# design.net
KiCad netlist of a schematic drawn in EasyEDA Pro
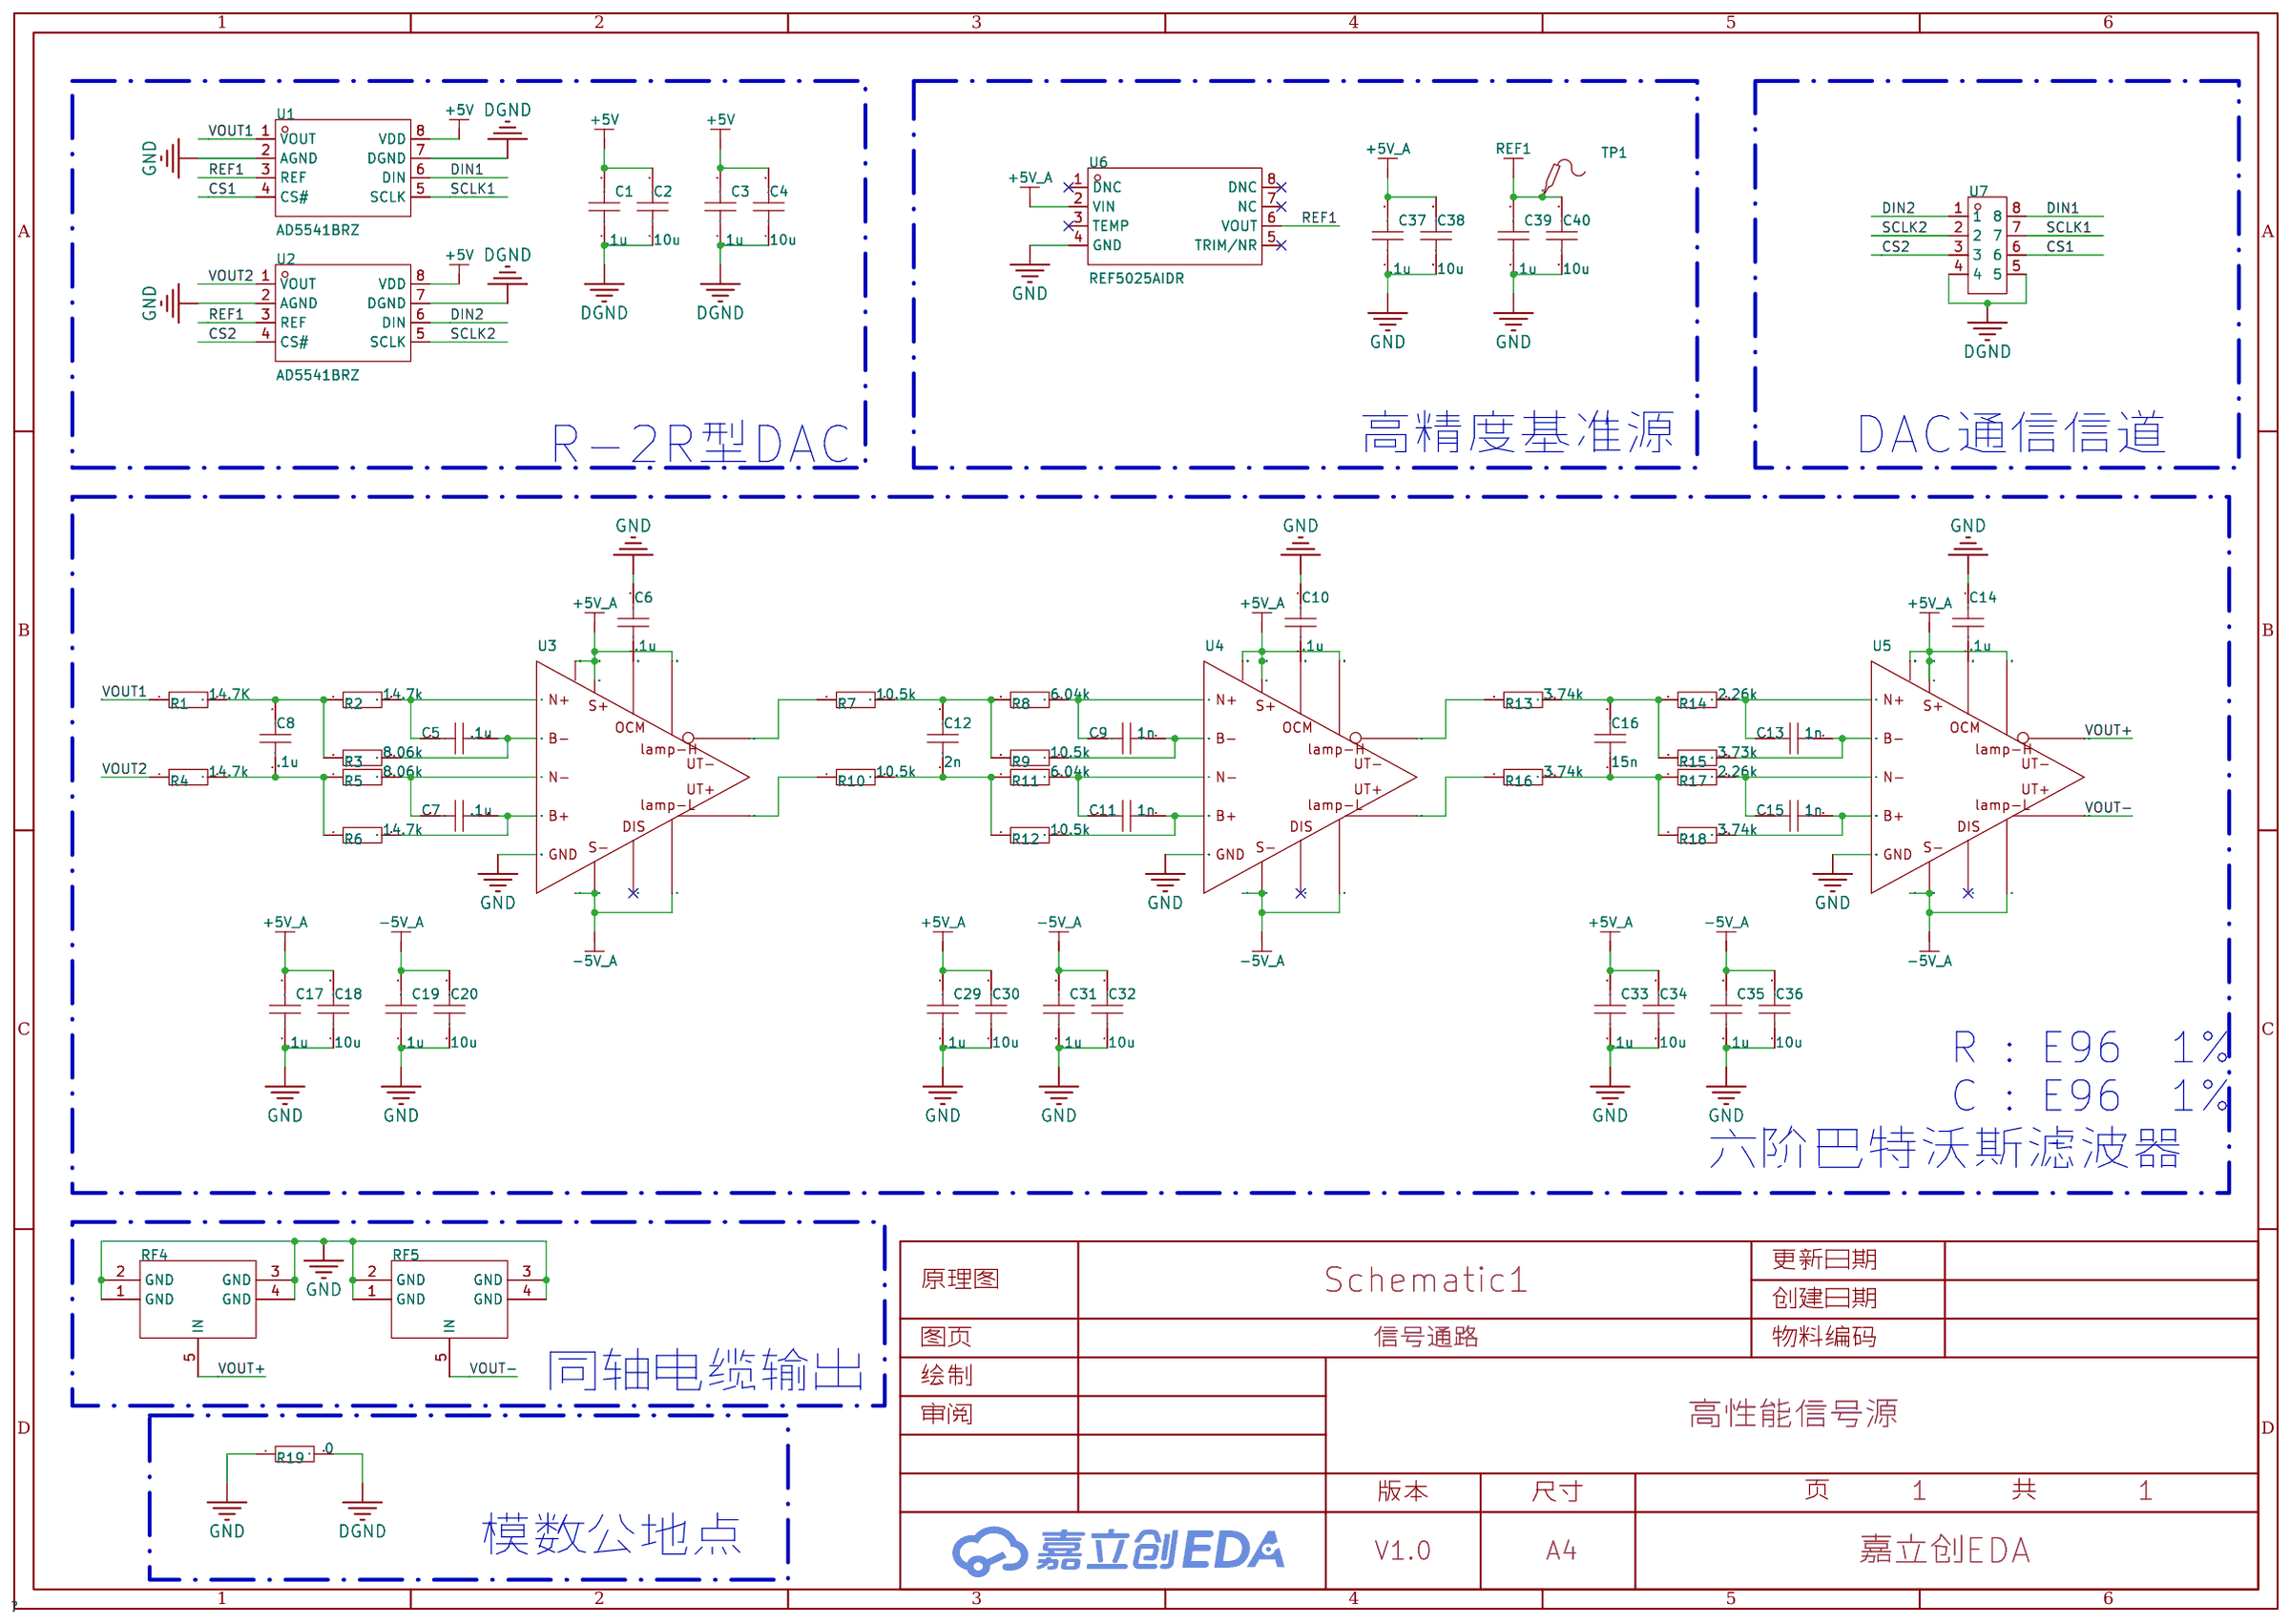
[diagram p0: 信号通路]
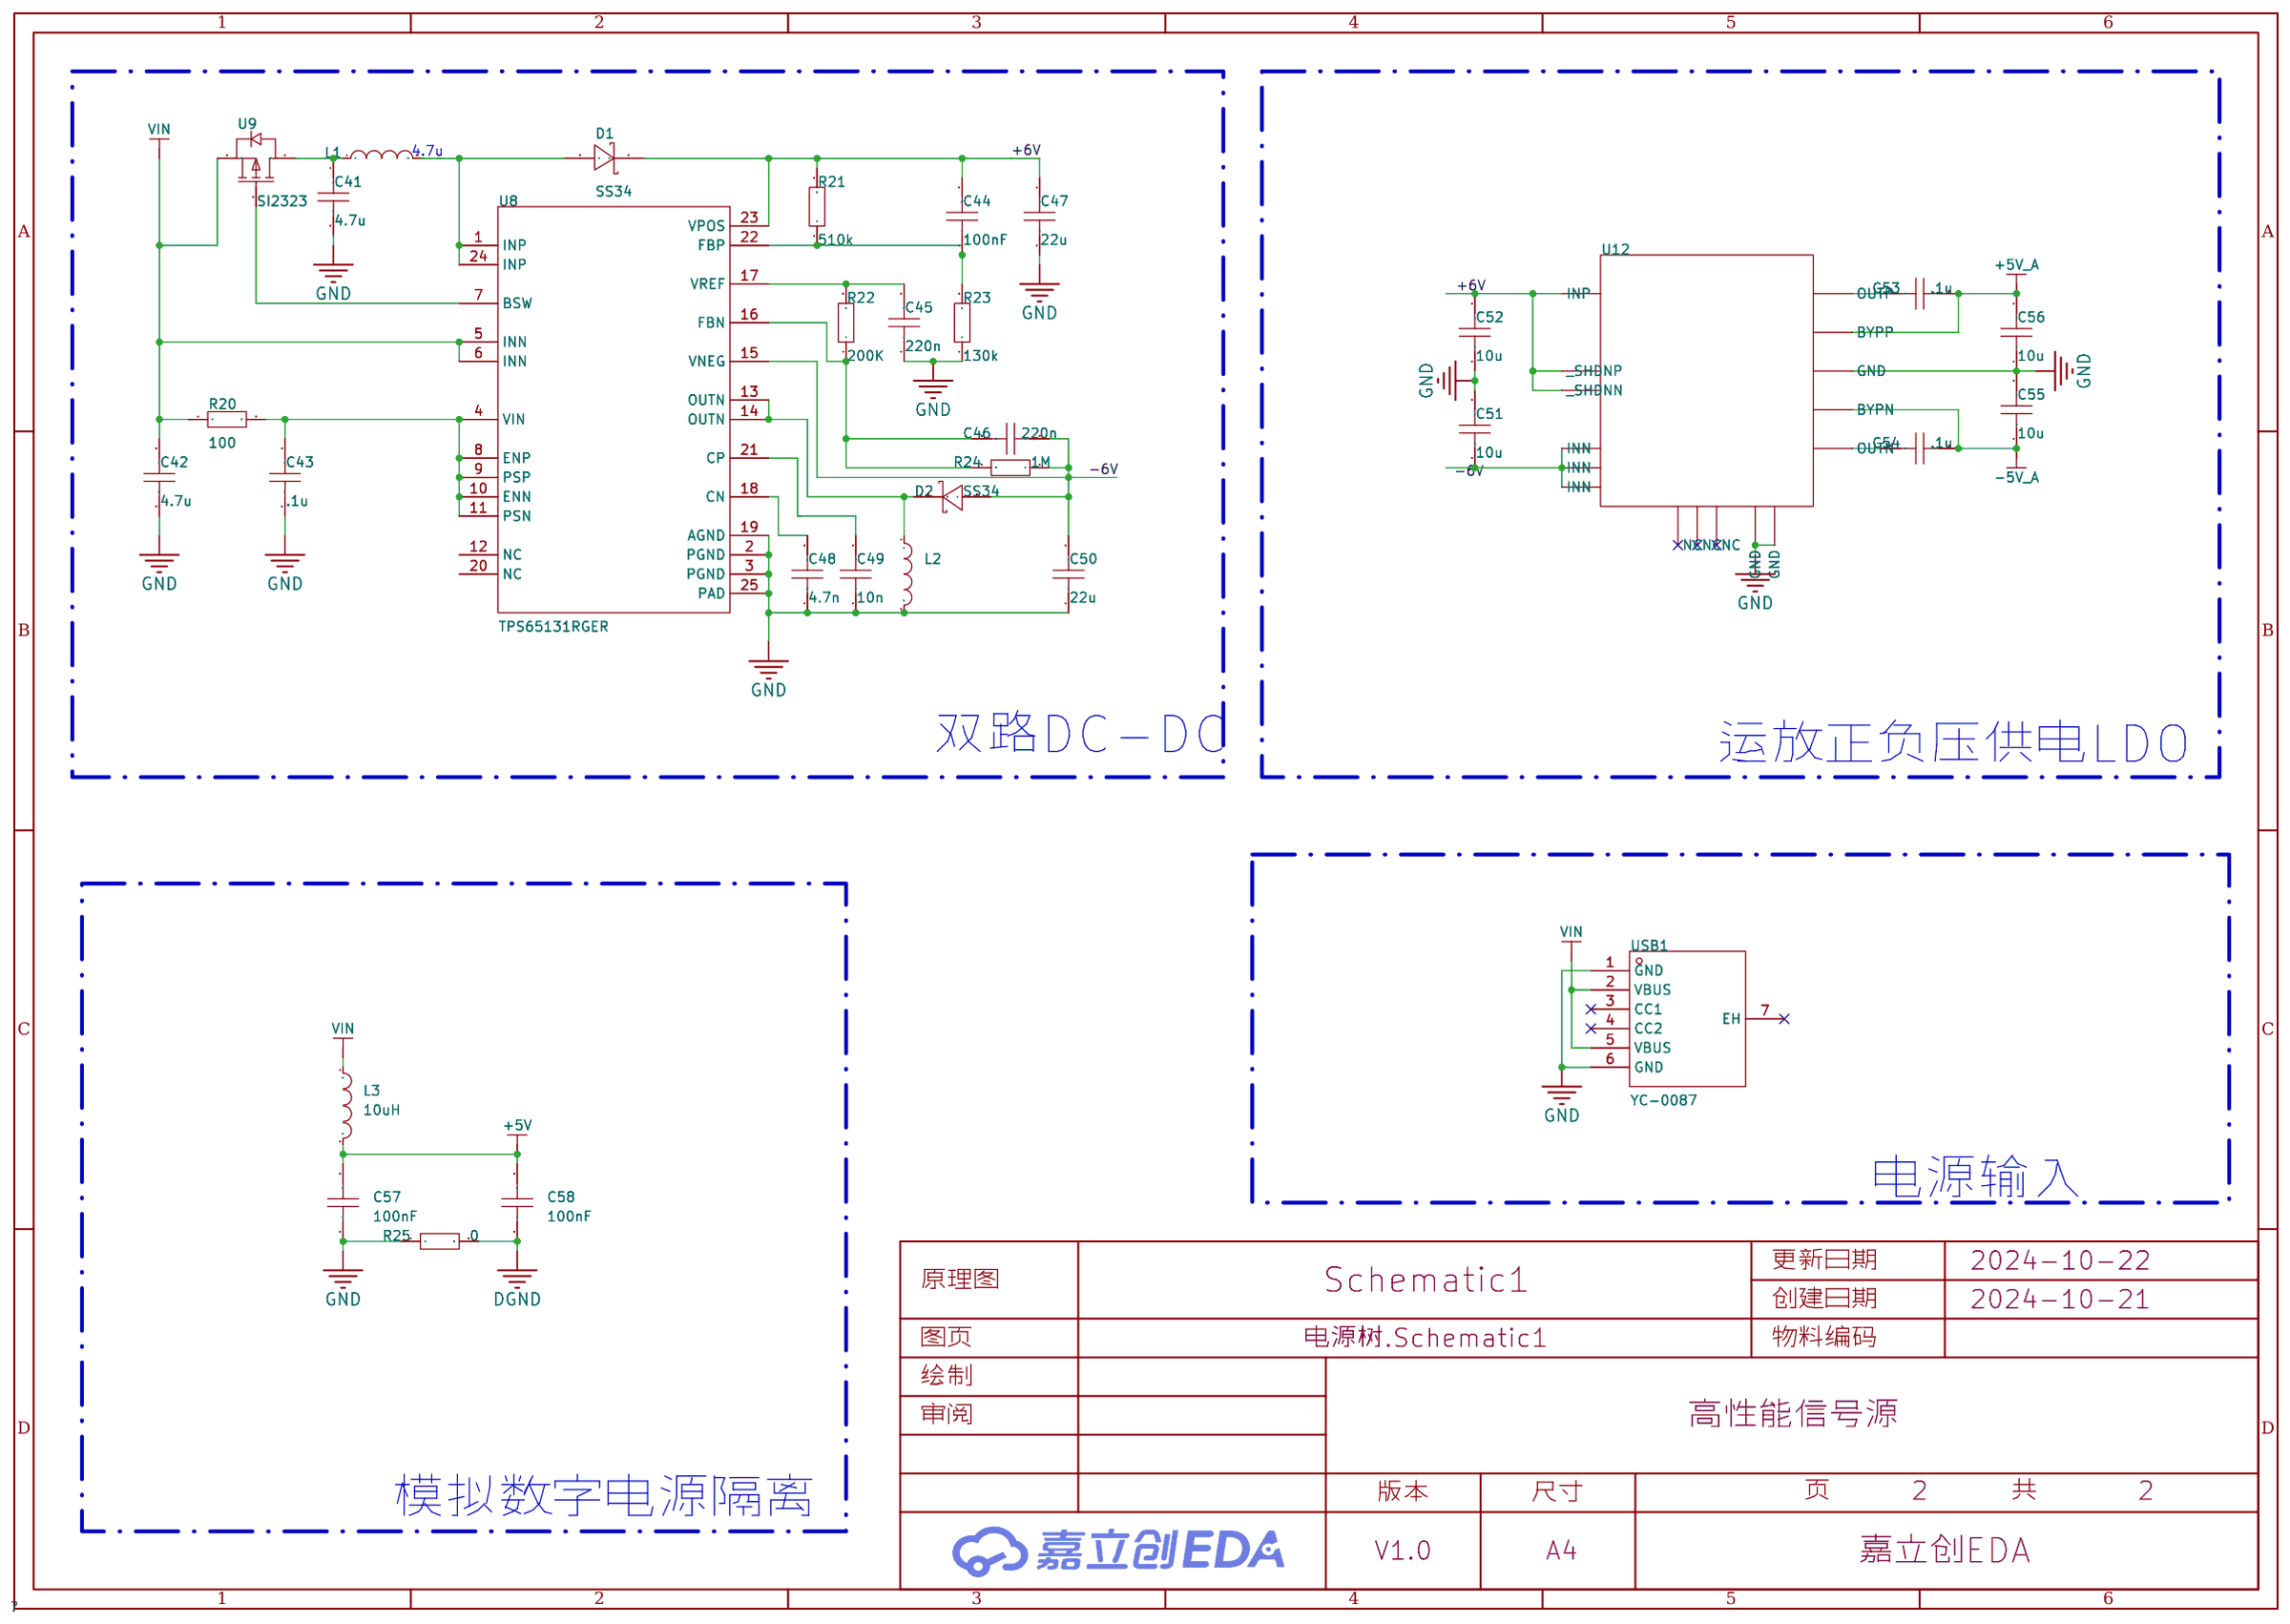
[diagram p1: 电源树]

(export (version "E")
  (design (tool "Eeschema 10.0.6"))
  (components
    (comp (ref "C1")
      (value ".1u")
      (footprint "easyedapro:C0603")
      (libsource (lib "easyedapro") (part "CapAcitance"))
    )
    (comp (ref "C2")
      (value "10u")
      (footprint "easyedapro:C0603")
      (libsource (lib "easyedapro") (part "CapAcitance"))
    )
    (comp (ref "C3")
      (value ".1u")
      (footprint "easyedapro:C0603")
      (libsource (lib "easyedapro") (part "CapAcitance"))
    )
    (comp (ref "C4")
      (value "10u")
      (footprint "easyedapro:C0603")
      (libsource (lib "easyedapro") (part "CapAcitance"))
    )
    (comp (ref "C5")
      (value ".1u")
      (footprint "easyedapro:C0603")
      (libsource (lib "easyedapro") (part "CapAcitance"))
    )
    (comp (ref "C6")
      (value ".1u")
      (footprint "easyedapro:C0603")
      (libsource (lib "easyedapro") (part "CapAcitance"))
    )
    (comp (ref "C7")
      (value ".1u")
      (footprint "easyedapro:C0603")
      (libsource (lib "easyedapro") (part "CapAcitance"))
    )
    (comp (ref "C8")
      (value ".1u")
      (footprint "easyedapro:C0603")
      (libsource (lib "easyedapro") (part "CapAcitance"))
    )
    (comp (ref "C9")
      (value "1n")
      (footprint "easyedapro:C0603")
      (libsource (lib "easyedapro") (part "CapAcitance"))
    )
    (comp (ref "C10")
      (value ".1u")
      (footprint "easyedapro:C0603")
      (libsource (lib "easyedapro") (part "CapAcitance"))
    )
    (comp (ref "C11")
      (value "1n")
      (footprint "easyedapro:C0603")
      (libsource (lib "easyedapro") (part "CapAcitance"))
    )
    (comp (ref "C12")
      (value "2n")
      (footprint "easyedapro:C0603")
      (libsource (lib "easyedapro") (part "CapAcitance"))
    )
    (comp (ref "C13")
      (value "1n")
      (footprint "easyedapro:C0603")
      (libsource (lib "easyedapro") (part "CapAcitance"))
    )
    (comp (ref "C14")
      (value ".1u")
      (footprint "easyedapro:C0603")
      (libsource (lib "easyedapro") (part "CapAcitance"))
    )
    (comp (ref "C15")
      (value "1n")
      (footprint "easyedapro:C0603")
      (libsource (lib "easyedapro") (part "CapAcitance"))
    )
    (comp (ref "C16")
      (value "15n")
      (footprint "easyedapro:C0603")
      (libsource (lib "easyedapro") (part "CapAcitance"))
    )
    (comp (ref "C17")
      (value ".1u")
      (footprint "easyedapro:C0603")
      (libsource (lib "easyedapro") (part "CapAcitance"))
    )
    (comp (ref "C18")
      (value "10u")
      (footprint "easyedapro:C0603")
      (libsource (lib "easyedapro") (part "CapAcitance"))
    )
    (comp (ref "C19")
      (value ".1u")
      (footprint "easyedapro:C0603")
      (libsource (lib "easyedapro") (part "CapAcitance"))
    )
    (comp (ref "C20")
      (value "10u")
      (footprint "easyedapro:C0603")
      (libsource (lib "easyedapro") (part "CapAcitance"))
    )
    (comp (ref "C29")
      (value ".1u")
      (footprint "easyedapro:C0603")
      (libsource (lib "easyedapro") (part "CapAcitance"))
    )
    (comp (ref "C30")
      (value "10u")
      (footprint "easyedapro:C0603")
      (libsource (lib "easyedapro") (part "CapAcitance"))
    )
    (comp (ref "C31")
      (value ".1u")
      (footprint "easyedapro:C0603")
      (libsource (lib "easyedapro") (part "CapAcitance"))
    )
    (comp (ref "C32")
      (value "10u")
      (footprint "easyedapro:C0603")
      (libsource (lib "easyedapro") (part "CapAcitance"))
    )
    (comp (ref "C33")
      (value ".1u")
      (footprint "easyedapro:C0603")
      (libsource (lib "easyedapro") (part "CapAcitance"))
    )
    (comp (ref "C34")
      (value "10u")
      (footprint "easyedapro:C0603")
      (libsource (lib "easyedapro") (part "CapAcitance"))
    )
    (comp (ref "C35")
      (value ".1u")
      (footprint "easyedapro:C0603")
      (libsource (lib "easyedapro") (part "CapAcitance"))
    )
    (comp (ref "C36")
      (value "10u")
      (footprint "easyedapro:C0603")
      (libsource (lib "easyedapro") (part "CapAcitance"))
    )
    (comp (ref "C37")
      (value ".1u")
      (footprint "easyedapro:C0603")
      (libsource (lib "easyedapro") (part "CapAcitance"))
    )
    (comp (ref "C38")
      (value "10u")
      (footprint "easyedapro:C0603")
      (libsource (lib "easyedapro") (part "CapAcitance"))
    )
    (comp (ref "C39")
      (value ".1u")
      (footprint "easyedapro:C0603")
      (libsource (lib "easyedapro") (part "CapAcitance"))
    )
    (comp (ref "C40")
      (value "10u")
      (footprint "easyedapro:C0603")
      (libsource (lib "easyedapro") (part "CapAcitance"))
    )
    (comp (ref "R1")
      (value "14.7K")
      (footprint "easyedapro:R0603")
      (libsource (lib "easyedapro") (part "电阻"))
    )
    (comp (ref "R2")
      (value "14.7k")
      (footprint "easyedapro:R0603")
      (libsource (lib "easyedapro") (part "电阻"))
    )
    (comp (ref "R3")
      (value "8.06k")
      (footprint "easyedapro:R0603")
      (libsource (lib "easyedapro") (part "电阻"))
    )
    (comp (ref "R4")
      (value "14.7k")
      (footprint "easyedapro:R0603")
      (libsource (lib "easyedapro") (part "电阻"))
    )
    (comp (ref "R5")
      (value "8.06k")
      (footprint "easyedapro:R0603")
      (libsource (lib "easyedapro") (part "电阻"))
    )
    (comp (ref "R6")
      (value "14.7k")
      (footprint "easyedapro:R0603")
      (libsource (lib "easyedapro") (part "电阻"))
    )
    (comp (ref "R7")
      (value "10.5k")
      (footprint "easyedapro:R0603")
      (libsource (lib "easyedapro") (part "电阻"))
    )
    (comp (ref "R8")
      (value "6.04k")
      (footprint "easyedapro:R0603")
      (libsource (lib "easyedapro") (part "电阻"))
    )
    (comp (ref "R9")
      (value "10.5k")
      (footprint "easyedapro:R0603")
      (libsource (lib "easyedapro") (part "电阻"))
    )
    (comp (ref "R10")
      (value "10.5k")
      (footprint "easyedapro:R0603")
      (libsource (lib "easyedapro") (part "电阻"))
    )
    (comp (ref "R11")
      (value "6.04k")
      (footprint "easyedapro:R0603")
      (libsource (lib "easyedapro") (part "电阻"))
    )
    (comp (ref "R12")
      (value "10.5k")
      (footprint "easyedapro:R0603")
      (libsource (lib "easyedapro") (part "电阻"))
    )
    (comp (ref "R13")
      (value "3.74k")
      (footprint "easyedapro:R0603")
      (libsource (lib "easyedapro") (part "电阻"))
    )
    (comp (ref "R14")
      (value "2.26k")
      (footprint "easyedapro:R0603")
      (libsource (lib "easyedapro") (part "电阻"))
    )
    (comp (ref "R15")
      (value "3.73k")
      (footprint "easyedapro:R0603")
      (libsource (lib "easyedapro") (part "电阻"))
    )
    (comp (ref "R16")
      (value "3.74k")
      (footprint "easyedapro:R0603")
      (libsource (lib "easyedapro") (part "电阻"))
    )
    (comp (ref "R17")
      (value "2.26k")
      (footprint "easyedapro:R0603")
      (libsource (lib "easyedapro") (part "电阻"))
    )
    (comp (ref "R18")
      (value "3.74k")
      (footprint "easyedapro:R0603")
      (libsource (lib "easyedapro") (part "电阻"))
    )
    (comp (ref "R19") (value "0") (footprint "easyedapro:R0603") (libsource (lib "easyedapro") (part "电阻")))
    (comp (ref "RF4")
      (value "KH-SMA-K513-G")
      (footprint "easyedapro:ANT-TH_KH-SMA-K513-G")
      (description "连接器类型:板端;接口类型:内孔;端口数量:1;接口直径:-;接口长度/高度:-;频率-最大值:6GHz;射频系列:SMA;阻抗:50Ω;样式:弯头;工作温度范围:-55°C~+155°C;")
      (fields (field (name "Manufacturer") "kinghelm(金航标)"))
      (libsource (lib "easyedapro") (part "KH-SMA-K513-G"))
    )
    (comp (ref "RF5")
      (value "KH-SMA-K513-G")
      (footprint "easyedapro:ANT-TH_KH-SMA-K513-G")
      (description "连接器类型:板端;接口类型:内孔;端口数量:1;接口直径:-;接口长度/高度:-;频率-最大值:6GHz;射频系列:SMA;阻抗:50Ω;样式:弯头;工作温度范围:-55°C~+155°C;")
      (fields (field (name "Manufacturer") "kinghelm(金航标)"))
      (libsource (lib "easyedapro") (part "KH-SMA-K513-G"))
    )
    (comp (ref "TP1")
      (value "~")
      (footprint "easyedapro:Test-Point-0.5mm")
      (description "Test Point 测试点")
      (libsource (lib "easyedapro") (part "Test-Point"))
    )
    (comp (ref "U1")
      (value "AD5541BRZ")
      (footprint "easyedapro:SOIC-8_L4.9-W3.9-P1.27-LS6.0-BL")
      (description "接口:DSP；SPI;电源电压:2.7V~5.5V;分辨率:16位;INL/DNL:±0.5LSB；±0.5LSB;稳定时间:1us;")
      (fields (field (name "Manufacturer") "ADI(亚德诺)"))
      (libsource (lib "easyedapro") (part "AD5541BRZ"))
    )
    (comp (ref "U2")
      (value "AD5541BRZ")
      (footprint "easyedapro:SOIC-8_L4.9-W3.9-P1.27-LS6.0-BL")
      (description "接口:DSP；SPI;电源电压:2.7V~5.5V;分辨率:16位;INL/DNL:±0.5LSB；±0.5LSB;稳定时间:1us;")
      (fields (field (name "Manufacturer") "ADI(亚德诺)"))
      (libsource (lib "easyedapro") (part "AD5541BRZ"))
    )
    (comp (ref "U3")
      (value "~")
      (footprint "easyedapro:LFCSP-16_L3.0-W3.0-P0.50-TL-EP1.6-1")
      (libsource (lib "easyedapro") (part "ADA4945-HP"))
    )
    (comp (ref "U4")
      (value "~")
      (footprint "easyedapro:LFCSP-16_L3.0-W3.0-P0.50-TL-EP1.6-1")
      (libsource (lib "easyedapro") (part "ADA4945-HP"))
    )
    (comp (ref "U5")
      (value "~")
      (footprint "easyedapro:LFCSP-16_L3.0-W3.0-P0.50-TL-EP1.6-1")
      (libsource (lib "easyedapro") (part "ADA4945-HP"))
    )
    (comp (ref "U6")
      (value "REF5025AIDR")
      (footprint "easyedapro:SOIC-8_L4.9-W3.9-P1.27-LS6.0-BL")
      (description "输出类型:固定;输入电压:2.7V~18V;输出电压:2.5V;输出电流:10mA;精度:±0.1%;")
      (fields (field (name "Manufacturer") "TI(德州仪器)"))
      (libsource (lib "easyedapro") (part "REF5025AIDR"))
    )
    (comp (ref "U7")
      (value "~")
      (footprint "easyedapro:母针座2.54 2X4")
      (libsource (lib "easyedapro") (part "母针座2.54 8P"))
    )
    (comp (ref "C41")
      (value "4.7u")
      (footprint "easyedapro:C0603")
      (libsource (lib "easyedapro") (part "CapAcitance"))
    )
    (comp (ref "C42")
      (value "4.7u")
      (footprint "easyedapro:C0603")
      (libsource (lib "easyedapro") (part "CapAcitance"))
    )
    (comp (ref "C43")
      (value ".1u")
      (footprint "easyedapro:C0603")
      (libsource (lib "easyedapro") (part "CapAcitance"))
    )
    (comp (ref "C44")
      (value "100nF")
      (footprint "easyedapro:C0603")
      (libsource (lib "easyedapro") (part "CapAcitance"))
    )
    (comp (ref "C45")
      (value "220n")
      (footprint "easyedapro:C0603")
      (libsource (lib "easyedapro") (part "CapAcitance"))
    )
    (comp (ref "C46")
      (value "220n")
      (footprint "easyedapro:C0603")
      (libsource (lib "easyedapro") (part "CapAcitance"))
    )
    (comp (ref "C47")
      (value "22u")
      (footprint "easyedapro:C0603")
      (libsource (lib "easyedapro") (part "CapAcitance"))
    )
    (comp (ref "C48")
      (value "4.7n")
      (footprint "easyedapro:C0603")
      (libsource (lib "easyedapro") (part "CapAcitance"))
    )
    (comp (ref "C49")
      (value "10n")
      (footprint "easyedapro:C0603")
      (libsource (lib "easyedapro") (part "CapAcitance"))
    )
    (comp (ref "C50")
      (value "22u")
      (footprint "easyedapro:C0603")
      (libsource (lib "easyedapro") (part "CapAcitance"))
    )
    (comp (ref "C51")
      (value "10u")
      (footprint "easyedapro:C0603")
      (libsource (lib "easyedapro") (part "CapAcitance"))
    )
    (comp (ref "C52")
      (value "10u")
      (footprint "easyedapro:C0603")
      (libsource (lib "easyedapro") (part "CapAcitance"))
    )
    (comp (ref "C53")
      (value ".1u")
      (footprint "easyedapro:C0603")
      (libsource (lib "easyedapro") (part "CapAcitance"))
    )
    (comp (ref "C54")
      (value ".1u")
      (footprint "easyedapro:C0603")
      (libsource (lib "easyedapro") (part "CapAcitance"))
    )
    (comp (ref "C55")
      (value "10u")
      (footprint "easyedapro:C0603")
      (libsource (lib "easyedapro") (part "CapAcitance"))
    )
    (comp (ref "C56")
      (value "10u")
      (footprint "easyedapro:C0603")
      (libsource (lib "easyedapro") (part "CapAcitance"))
    )
    (comp (ref "C57")
      (value "100nF")
      (footprint "easyedapro:C0603")
      (libsource (lib "easyedapro") (part "CapAcitance"))
    )
    (comp (ref "C58")
      (value "100nF")
      (footprint "easyedapro:C0603")
      (libsource (lib "easyedapro") (part "CapAcitance"))
    )
    (comp (ref "D1")
      (value "SS34")
      (footprint "easyedapro:SMA_L4.3-W2.6-LS5.2-RD")
      (description "二极管配置:独立式;正向压降(Vf):550mV@3A;直流反向耐压(Vr):40V;整流电流:3A;")
      (fields (field (name "Manufacturer") "MDD(辰达半导体)"))
      (libsource (lib "easyedapro") (part "SS34_C8678"))
    )
    (comp (ref "D2")
      (value "SS34")
      (footprint "easyedapro:SMA_L4.3-W2.6-LS5.2-RD")
      (description "二极管配置:独立式;正向压降(Vf):550mV@3A;直流反向耐压(Vr):40V;整流电流:3A;")
      (fields (field (name "Manufacturer") "MDD(辰达半导体)"))
      (libsource (lib "easyedapro") (part "SS34_C8678"))
    )
    (comp (ref "L1")
      (value "~")
      (footprint "easyedapro:IND-SMD_L7.1-W6.6")
      (fields
        (field (name "Manufacturer Part") "PSPMAA0603H-470M-ANF")
        (field (name "Manufacturer") "PROD(谱罗德)")
      )
      (libsource (lib "easyedapro") (part "PSPMAA0603H-470M-ANF"))
    )
    (comp (ref "L2")
      (value "~")
      (footprint "easyedapro:IND-SMD_L7.1-W6.6")
      (fields
        (field (name "Manufacturer Part") "PSPMAA0603H-470M-ANF")
        (field (name "Manufacturer") "PROD(谱罗德)")
      )
      (libsource (lib "easyedapro") (part "PSPMAA0603H-470M-ANF"))
    )
    (comp (ref "L3")
      (value "10uH")
      (footprint "easyedapro:L0603")
      (libsource (lib "easyedapro") (part "SDFL1608S100KTF"))
    )
    (comp (ref "R20") (value "100") (footprint "easyedapro:R0603") (libsource (lib "easyedapro") (part "电阻")))
    (comp (ref "R21")
      (value "510k")
      (footprint "easyedapro:R0603")
      (libsource (lib "easyedapro") (part "电阻"))
    )
    (comp (ref "R22")
      (value "200K")
      (footprint "easyedapro:R0603")
      (libsource (lib "easyedapro") (part "电阻"))
    )
    (comp (ref "R23")
      (value "130k")
      (footprint "easyedapro:R0603")
      (libsource (lib "easyedapro") (part "电阻"))
    )
    (comp (ref "R24") (value "1M") (footprint "easyedapro:R0603") (libsource (lib "easyedapro") (part "电阻")))
    (comp (ref "R25") (value "0") (footprint "easyedapro:R0603") (libsource (lib "easyedapro") (part "电阻")))
    (comp (ref "U8")
      (value "TPS65131RGER")
      (footprint "easyedapro:QFN-24_L4.0-W4.0-P0.50-TL-EP2.6")
      (libsource (lib "easyedapro") (part "TPS65131"))
    )
    (comp (ref "U9")
      (value "SI2323")
      (footprint "easyedapro:SOT-23-3_L2.9-W1.6-P1.90-LS2.8-BR")
      (fields (field (name "Manufacturer") "TECH PUBLIC(台舟)"))
      (libsource (lib "easyedapro") (part "SI2323DDS"))
    )
    (comp (ref "U12")
      (value "~")
      (footprint "easyedapro:DFN-14_L4.0-W3.0-P0.50-BL-EP_LT3032MPDE-PBF")
      (libsource (lib "easyedapro") (part "LT3032"))
    )
    (comp (ref "USB1")
      (value "YC-0087")
      (footprint "easyedapro:type-c-smd_type-c-6p-3")
      (libsource (lib "easyedapro") (part "YC-0087"))
    )
  )
  (nets
    (net (code "1") (name "+5V") (class "Default")
      (node (ref "C1") (pin "2") (pinfunction "2_2") (pintype "input"))
      (node (ref "C2") (pin "2") (pinfunction "2_2") (pintype "input"))
      (node (ref "C3") (pin "2") (pinfunction "2_2") (pintype "input"))
      (node (ref "C4") (pin "2") (pinfunction "2_2") (pintype "input"))
      (node (ref "C57") (pin "2") (pinfunction "2_2") (pintype "input"))
      (node (ref "C58") (pin "2") (pinfunction "2_2") (pintype "input"))
      (node (ref "L3") (pin "2") (pinfunction "2_2") (pintype "unspecified"))
      (node (ref "U1") (pin "8") (pinfunction "VDD_8") (pintype "unspecified"))
      (node (ref "U2") (pin "8") (pinfunction "VDD_8") (pintype "unspecified"))
    )
    (net (code "2") (name "+5V_A") (class "Default")
      (node (ref "C17") (pin "2") (pinfunction "2_2") (pintype "input"))
      (node (ref "C18") (pin "2") (pinfunction "2_2") (pintype "input"))
      (node (ref "C29") (pin "2") (pinfunction "2_2") (pintype "input"))
      (node (ref "C30") (pin "2") (pinfunction "2_2") (pintype "input"))
      (node (ref "C33") (pin "2") (pinfunction "2_2") (pintype "input"))
      (node (ref "C34") (pin "2") (pinfunction "2_2") (pintype "input"))
      (node (ref "C37") (pin "2") (pinfunction "2_2") (pintype "input"))
      (node (ref "C38") (pin "2") (pinfunction "2_2") (pintype "input"))
      (node (ref "C53") (pin "2") (pinfunction "2_2") (pintype "input"))
      (node (ref "C56") (pin "2") (pinfunction "2_2") (pintype "input"))
      (node (ref "U12") (pin "3") (pinfunction "BYPP_3") (pintype "input"))
      (node (ref "U3") (pin "5") (pinfunction "MODE_5") (pintype "input"))
      (node (ref "U3") (pin "6") (pinfunction "S+_6") (pintype "input"))
      (node (ref "U3") (pin "7") (pinfunction "S+_7") (pintype "input"))
      (node (ref "U3") (pin "8") (pinfunction "LAMPH_8") (pintype "input"))
      (node (ref "U4") (pin "5") (pinfunction "MODE_5") (pintype "input"))
      (node (ref "U4") (pin "6") (pinfunction "S+_6") (pintype "input"))
      (node (ref "U4") (pin "7") (pinfunction "S+_7") (pintype "input"))
      (node (ref "U4") (pin "8") (pinfunction "LAMPH_8") (pintype "input"))
      (node (ref "U5") (pin "5") (pinfunction "MODE_5") (pintype "input"))
      (node (ref "U5") (pin "6") (pinfunction "S+_6") (pintype "input"))
      (node (ref "U5") (pin "7") (pinfunction "S+_7") (pintype "input"))
      (node (ref "U5") (pin "8") (pinfunction "LAMPH_8") (pintype "input"))
      (node (ref "U6") (pin "2") (pinfunction "VIN_2") (pintype "unspecified"))
    )
    (net (code "3") (name "+6V") (class "Default")
      (node (ref "C44") (pin "2") (pinfunction "2_2") (pintype "input"))
      (node (ref "C47") (pin "2") (pinfunction "2_2") (pintype "input"))
      (node (ref "C52") (pin "2") (pinfunction "2_2") (pintype "input"))
      (node (ref "D1") (pin "1") (pinfunction "K_1") (pintype "unspecified"))
      (node (ref "R21") (pin "2") (pinfunction "2_2") (pintype "input"))
      (node (ref "U12") (pin "10") (pinfunction "_SHDNN_10") (pintype "input"))
      (node (ref "U12") (pin "12") (pinfunction "_SHDNP_12") (pintype "input"))
      (node (ref "U12") (pin "14") (pinfunction "INP_14") (pintype "input"))
      (node (ref "U8") (pin "23") (pinfunction "VPOS_23") (pintype "input"))
    )
    (net (code "4") (name "-5V_A") (class "Default")
      (node (ref "C19") (pin "2") (pinfunction "2_2") (pintype "input"))
      (node (ref "C20") (pin "2") (pinfunction "2_2") (pintype "input"))
      (node (ref "C31") (pin "2") (pinfunction "2_2") (pintype "input"))
      (node (ref "C32") (pin "2") (pinfunction "2_2") (pintype "input"))
      (node (ref "C35") (pin "2") (pinfunction "2_2") (pintype "input"))
      (node (ref "C36") (pin "2") (pinfunction "2_2") (pintype "input"))
      (node (ref "C54") (pin "2") (pinfunction "2_2") (pintype "input"))
      (node (ref "C55") (pin "1") (pinfunction "1_1") (pintype "input"))
      (node (ref "U12") (pin "11") (pinfunction "BYPN_11") (pintype "input"))
      (node (ref "U3") (pin "13") (pinfunction "LAMPL_13") (pintype "input"))
      (node (ref "U3") (pin "14") (pinfunction "S-_14") (pintype "input"))
      (node (ref "U3") (pin "15") (pinfunction "S-_15") (pintype "input"))
      (node (ref "U4") (pin "13") (pinfunction "LAMPL_13") (pintype "input"))
      (node (ref "U4") (pin "14") (pinfunction "S-_14") (pintype "input"))
      (node (ref "U4") (pin "15") (pinfunction "S-_15") (pintype "input"))
      (node (ref "U5") (pin "13") (pinfunction "LAMPL_13") (pintype "input"))
      (node (ref "U5") (pin "14") (pinfunction "S-_14") (pintype "input"))
      (node (ref "U5") (pin "15") (pinfunction "S-_15") (pintype "input"))
    )
    (net (code "5") (name "-6V") (class "Default")
      (node (ref "C46") (pin "1") (pinfunction "1_1") (pintype "input"))
      (node (ref "C50") (pin "2") (pinfunction "2_2") (pintype "input"))
      (node (ref "C51") (pin "1") (pinfunction "1_1") (pintype "input"))
      (node (ref "D2") (pin "2") (pinfunction "A_2") (pintype "unspecified"))
      (node (ref "R24") (pin "1") (pinfunction "1_1") (pintype "input"))
      (node (ref "U12") (pin "16") (pinfunction "INN_16") (pintype "input"))
      (node (ref "U12") (pin "6") (pinfunction "INN_6") (pintype "input"))
      (node (ref "U12") (pin "9") (pinfunction "INN_9") (pintype "input"))
      (node (ref "U8") (pin "15") (pinfunction "VNEG_15") (pintype "input"))
    )
    (net (code "6") (name "CS1") (class "Default")
      (node (ref "U1") (pin "4") (pinfunction "CS#_4") (pintype "unspecified"))
      (node (ref "U7") (pin "6") (pinfunction "6_6") (pintype "input"))
    )
    (net (code "7") (name "CS2") (class "Default")
      (node (ref "U2") (pin "4") (pinfunction "CS#_4") (pintype "unspecified"))
      (node (ref "U7") (pin "3") (pinfunction "3_3") (pintype "input"))
    )
    (net (code "8") (name "DGND") (class "Default")
      (node (ref "C1") (pin "1") (pinfunction "1_1") (pintype "input"))
      (node (ref "C2") (pin "1") (pinfunction "1_1") (pintype "input"))
      (node (ref "C3") (pin "1") (pinfunction "1_1") (pintype "input"))
      (node (ref "C4") (pin "1") (pinfunction "1_1") (pintype "input"))
      (node (ref "C58") (pin "1") (pinfunction "1_1") (pintype "input"))
      (node (ref "R19") (pin "2") (pinfunction "2_2") (pintype "input"))
      (node (ref "R25") (pin "2") (pinfunction "2_2") (pintype "input"))
      (node (ref "U1") (pin "7") (pinfunction "DGND_7") (pintype "unspecified"))
      (node (ref "U2") (pin "7") (pinfunction "DGND_7") (pintype "unspecified"))
      (node (ref "U7") (pin "4") (pinfunction "4_4") (pintype "input"))
      (node (ref "U7") (pin "5") (pinfunction "5_5") (pintype "input"))
    )
    (net (code "9") (name "DIN1") (class "Default")
      (node (ref "U1") (pin "6") (pinfunction "DIN_6") (pintype "unspecified"))
      (node (ref "U7") (pin "8") (pinfunction "8_8") (pintype "input"))
    )
    (net (code "10") (name "DIN2") (class "Default")
      (node (ref "U2") (pin "6") (pinfunction "DIN_6") (pintype "unspecified"))
      (node (ref "U7") (pin "1") (pinfunction "1_1") (pintype "input"))
    )
    (net (code "11") (name "GND") (class "Default")
      (node (ref "C10") (pin "2") (pinfunction "2_2") (pintype "input"))
      (node (ref "C14") (pin "2") (pinfunction "2_2") (pintype "input"))
      (node (ref "C17") (pin "1") (pinfunction "1_1") (pintype "input"))
      (node (ref "C18") (pin "1") (pinfunction "1_1") (pintype "input"))
      (node (ref "C19") (pin "1") (pinfunction "1_1") (pintype "input"))
      (node (ref "C20") (pin "1") (pinfunction "1_1") (pintype "input"))
      (node (ref "C29") (pin "1") (pinfunction "1_1") (pintype "input"))
      (node (ref "C30") (pin "1") (pinfunction "1_1") (pintype "input"))
      (node (ref "C31") (pin "1") (pinfunction "1_1") (pintype "input"))
      (node (ref "C32") (pin "1") (pinfunction "1_1") (pintype "input"))
      (node (ref "C33") (pin "1") (pinfunction "1_1") (pintype "input"))
      (node (ref "C34") (pin "1") (pinfunction "1_1") (pintype "input"))
      (node (ref "C35") (pin "1") (pinfunction "1_1") (pintype "input"))
      (node (ref "C36") (pin "1") (pinfunction "1_1") (pintype "input"))
      (node (ref "C37") (pin "1") (pinfunction "1_1") (pintype "input"))
      (node (ref "C38") (pin "1") (pinfunction "1_1") (pintype "input"))
      (node (ref "C39") (pin "1") (pinfunction "1_1") (pintype "input"))
      (node (ref "C40") (pin "1") (pinfunction "1_1") (pintype "input"))
      (node (ref "C41") (pin "2") (pinfunction "2_2") (pintype "input"))
      (node (ref "C42") (pin "2") (pinfunction "2_2") (pintype "input"))
      (node (ref "C43") (pin "2") (pinfunction "2_2") (pintype "input"))
      (node (ref "C45") (pin "1") (pinfunction "1_1") (pintype "input"))
      (node (ref "C47") (pin "1") (pinfunction "1_1") (pintype "input"))
      (node (ref "C48") (pin "1") (pinfunction "1_1") (pintype "input"))
      (node (ref "C49") (pin "1") (pinfunction "1_1") (pintype "input"))
      (node (ref "C50") (pin "1") (pinfunction "1_1") (pintype "input"))
      (node (ref "C51") (pin "2") (pinfunction "2_2") (pintype "input"))
      (node (ref "C52") (pin "1") (pinfunction "1_1") (pintype "input"))
      (node (ref "C55") (pin "2") (pinfunction "2_2") (pintype "input"))
      (node (ref "C56") (pin "1") (pinfunction "1_1") (pintype "input"))
      (node (ref "C57") (pin "1") (pinfunction "1_1") (pintype "input"))
      (node (ref "C6") (pin "2") (pinfunction "2_2") (pintype "input"))
      (node (ref "L2") (pin "2") (pinfunction "2_2") (pintype "unspecified"))
      (node (ref "R19") (pin "1") (pinfunction "1_1") (pintype "input"))
      (node (ref "R23") (pin "1") (pinfunction "1_1") (pintype "input"))
      (node (ref "R25") (pin "1") (pinfunction "1_1") (pintype "input"))
      (node (ref "RF4") (pin "1") (pinfunction "GND_1") (pintype "unspecified"))
      (node (ref "RF4") (pin "2") (pinfunction "GND_2") (pintype "unspecified"))
      (node (ref "RF4") (pin "3") (pinfunction "GND_3") (pintype "unspecified"))
      (node (ref "RF4") (pin "4") (pinfunction "GND_4") (pintype "unspecified"))
      (node (ref "RF5") (pin "1") (pinfunction "GND_1") (pintype "unspecified"))
      (node (ref "RF5") (pin "2") (pinfunction "GND_2") (pintype "unspecified"))
      (node (ref "RF5") (pin "3") (pinfunction "GND_3") (pintype "unspecified"))
      (node (ref "RF5") (pin "4") (pinfunction "GND_4") (pintype "unspecified"))
      (node (ref "U1") (pin "2") (pinfunction "AGND_2") (pintype "unspecified"))
      (node (ref "U12") (pin "15") (pinfunction "GND_15") (pintype "input"))
      (node (ref "U12") (pin "4") (pinfunction "GND_4") (pintype "input"))
      (node (ref "U12") (pin "5") (pinfunction "GND_5") (pintype "input"))
      (node (ref "U2") (pin "2") (pinfunction "AGND_2") (pintype "unspecified"))
      (node (ref "U3") (pin "16") (pinfunction "GND_16") (pintype "input"))
      (node (ref "U4") (pin "16") (pinfunction "GND_16") (pintype "input"))
      (node (ref "U5") (pin "16") (pinfunction "GND_16") (pintype "input"))
      (node (ref "U6") (pin "4") (pinfunction "GND_4") (pintype "unspecified"))
      (node (ref "U8") (pin "19") (pinfunction "AGND_19") (pintype "unspecified"))
      (node (ref "U8") (pin "2") (pinfunction "PGND_2") (pintype "unspecified"))
      (node (ref "U8") (pin "25") (pinfunction "PAD_25") (pintype "unspecified"))
      (node (ref "U8") (pin "3") (pinfunction "PGND_3") (pintype "unspecified"))
      (node (ref "USB1") (pin "1") (pinfunction "GND_1") (pintype "unspecified"))
      (node (ref "USB1") (pin "6") (pinfunction "GND_6") (pintype "unspecified"))
    )
    (net (code "12") (name "Net-(C8-Pad1)") (class "Default")
      (node (ref "C8") (pin "1") (pinfunction "1_1") (pintype "input"))
      (node (ref "R4") (pin "2") (pinfunction "2_2") (pintype "input"))
      (node (ref "R5") (pin "1") (pinfunction "1_1") (pintype "input"))
      (node (ref "R6") (pin "1") (pinfunction "1_1") (pintype "input"))
    )
    (net (code "13") (name "Net-(C8-Pad2)") (class "Default")
      (node (ref "C8") (pin "2") (pinfunction "2_2") (pintype "input"))
      (node (ref "R1") (pin "2") (pinfunction "2_2") (pintype "input"))
      (node (ref "R2") (pin "1") (pinfunction "1_1") (pintype "input"))
      (node (ref "R3") (pin "1") (pinfunction "1_1") (pintype "input"))
    )
    (net (code "14") (name "Net-(C12-Pad1)") (class "Default")
      (node (ref "C12") (pin "1") (pinfunction "1_1") (pintype "input"))
      (node (ref "R10") (pin "2") (pinfunction "2_2") (pintype "input"))
      (node (ref "R11") (pin "1") (pinfunction "1_1") (pintype "input"))
      (node (ref "R12") (pin "1") (pinfunction "1_1") (pintype "input"))
    )
    (net (code "15") (name "Net-(C12-Pad2)") (class "Default")
      (node (ref "C12") (pin "2") (pinfunction "2_2") (pintype "input"))
      (node (ref "R7") (pin "2") (pinfunction "2_2") (pintype "input"))
      (node (ref "R8") (pin "1") (pinfunction "1_1") (pintype "input"))
      (node (ref "R9") (pin "1") (pinfunction "1_1") (pintype "input"))
    )
    (net (code "16") (name "Net-(C16-Pad1)") (class "Default")
      (node (ref "C16") (pin "1") (pinfunction "1_1") (pintype "input"))
      (node (ref "R16") (pin "2") (pinfunction "2_2") (pintype "input"))
      (node (ref "R17") (pin "1") (pinfunction "1_1") (pintype "input"))
      (node (ref "R18") (pin "1") (pinfunction "1_1") (pintype "input"))
    )
    (net (code "17") (name "Net-(C16-Pad2)") (class "Default")
      (node (ref "C16") (pin "2") (pinfunction "2_2") (pintype "input"))
      (node (ref "R13") (pin "2") (pinfunction "2_2") (pintype "input"))
      (node (ref "R14") (pin "1") (pinfunction "1_1") (pintype "input"))
      (node (ref "R15") (pin "1") (pinfunction "1_1") (pintype "input"))
    )
    (net (code "18") (name "Net-(D1-A)") (class "Default")
      (node (ref "D1") (pin "2") (pinfunction "A_2") (pintype "unspecified"))
      (node (ref "L1") (pin "2") (pinfunction "2_2") (pintype "unspecified"))
      (node (ref "U8") (pin "1") (pinfunction "INP_1") (pintype "unspecified"))
      (node (ref "U8") (pin "24") (pinfunction "INP_24") (pintype "unspecified"))
    )
    (net (code "19") (name "Net-(D2-K)") (class "Default")
      (node (ref "D2") (pin "1") (pinfunction "K_1") (pintype "unspecified"))
      (node (ref "L2") (pin "1") (pinfunction "1_1") (pintype "unspecified"))
      (node (ref "U8") (pin "13") (pinfunction "OUTN_13") (pintype "unspecified"))
      (node (ref "U8") (pin "14") (pinfunction "OUTN_14") (pintype "unspecified"))
    )
    (net (code "20") (name "Net-(U3-FB+)") (class "Default")
      (node (ref "C7") (pin "2") (pinfunction "2_2") (pintype "input"))
      (node (ref "R6") (pin "2") (pinfunction "2_2") (pintype "input"))
      (node (ref "U3") (pin "4") (pinfunction "FB+_4") (pintype "input"))
    )
    (net (code "21") (name "Net-(U3-FB-)") (class "Default")
      (node (ref "C5") (pin "2") (pinfunction "2_2") (pintype "input"))
      (node (ref "R3") (pin "2") (pinfunction "2_2") (pintype "input"))
      (node (ref "U3") (pin "1") (pinfunction "FB-_1") (pintype "input"))
    )
    (net (code "22") (name "Net-(U3-IN+)") (class "Default")
      (node (ref "C5") (pin "1") (pinfunction "1_1") (pintype "input"))
      (node (ref "R2") (pin "2") (pinfunction "2_2") (pintype "input"))
      (node (ref "U3") (pin "2") (pinfunction "IN+_2") (pintype "input"))
    )
    (net (code "23") (name "Net-(U3-IN-)") (class "Default")
      (node (ref "C7") (pin "1") (pinfunction "1_1") (pintype "input"))
      (node (ref "R5") (pin "2") (pinfunction "2_2") (pintype "input"))
      (node (ref "U3") (pin "3") (pinfunction "IN-_3") (pintype "input"))
    )
    (net (code "24") (name "Net-(U3-OCM)") (class "Default")
      (node (ref "C6") (pin "1") (pinfunction "1_1") (pintype "input"))
      (node (ref "U3") (pin "9") (pinfunction "OCM_9") (pintype "input"))
    )
    (net (code "25") (name "Net-(U3-OUT+)") (class "Default")
      (node (ref "R10") (pin "1") (pinfunction "1_1") (pintype "input"))
      (node (ref "U3") (pin "10") (pinfunction "OUT+_10") (pintype "input"))
    )
    (net (code "26") (name "Net-(U3-OUT-)") (class "Default")
      (node (ref "R7") (pin "1") (pinfunction "1_1") (pintype "input"))
      (node (ref "U3") (pin "11") (pinfunction "OUT-_11") (pintype "input"))
    )
    (net (code "27") (name "Net-(U4-FB+)") (class "Default")
      (node (ref "C11") (pin "2") (pinfunction "2_2") (pintype "input"))
      (node (ref "R12") (pin "2") (pinfunction "2_2") (pintype "input"))
      (node (ref "U4") (pin "4") (pinfunction "FB+_4") (pintype "input"))
    )
    (net (code "28") (name "Net-(U4-FB-)") (class "Default")
      (node (ref "C9") (pin "2") (pinfunction "2_2") (pintype "input"))
      (node (ref "R9") (pin "2") (pinfunction "2_2") (pintype "input"))
      (node (ref "U4") (pin "1") (pinfunction "FB-_1") (pintype "input"))
    )
    (net (code "29") (name "Net-(U4-IN+)") (class "Default")
      (node (ref "C9") (pin "1") (pinfunction "1_1") (pintype "input"))
      (node (ref "R8") (pin "2") (pinfunction "2_2") (pintype "input"))
      (node (ref "U4") (pin "2") (pinfunction "IN+_2") (pintype "input"))
    )
    (net (code "30") (name "Net-(U4-IN-)") (class "Default")
      (node (ref "C11") (pin "1") (pinfunction "1_1") (pintype "input"))
      (node (ref "R11") (pin "2") (pinfunction "2_2") (pintype "input"))
      (node (ref "U4") (pin "3") (pinfunction "IN-_3") (pintype "input"))
    )
    (net (code "31") (name "Net-(U4-OCM)") (class "Default")
      (node (ref "C10") (pin "1") (pinfunction "1_1") (pintype "input"))
      (node (ref "U4") (pin "9") (pinfunction "OCM_9") (pintype "input"))
    )
    (net (code "32") (name "Net-(U4-OUT+)") (class "Default")
      (node (ref "R16") (pin "1") (pinfunction "1_1") (pintype "input"))
      (node (ref "U4") (pin "10") (pinfunction "OUT+_10") (pintype "input"))
    )
    (net (code "33") (name "Net-(U4-OUT-)") (class "Default")
      (node (ref "R13") (pin "1") (pinfunction "1_1") (pintype "input"))
      (node (ref "U4") (pin "11") (pinfunction "OUT-_11") (pintype "input"))
    )
    (net (code "34") (name "Net-(U5-FB+)") (class "Default")
      (node (ref "C15") (pin "2") (pinfunction "2_2") (pintype "input"))
      (node (ref "R18") (pin "2") (pinfunction "2_2") (pintype "input"))
      (node (ref "U5") (pin "4") (pinfunction "FB+_4") (pintype "input"))
    )
    (net (code "35") (name "Net-(U5-FB-)") (class "Default")
      (node (ref "C13") (pin "2") (pinfunction "2_2") (pintype "input"))
      (node (ref "R15") (pin "2") (pinfunction "2_2") (pintype "input"))
      (node (ref "U5") (pin "1") (pinfunction "FB-_1") (pintype "input"))
    )
    (net (code "36") (name "Net-(U5-IN+)") (class "Default")
      (node (ref "C13") (pin "1") (pinfunction "1_1") (pintype "input"))
      (node (ref "R14") (pin "2") (pinfunction "2_2") (pintype "input"))
      (node (ref "U5") (pin "2") (pinfunction "IN+_2") (pintype "input"))
    )
    (net (code "37") (name "Net-(U5-IN-)") (class "Default")
      (node (ref "C15") (pin "1") (pinfunction "1_1") (pintype "input"))
      (node (ref "R17") (pin "2") (pinfunction "2_2") (pintype "input"))
      (node (ref "U5") (pin "3") (pinfunction "IN-_3") (pintype "input"))
    )
    (net (code "38") (name "Net-(U5-OCM)") (class "Default")
      (node (ref "C14") (pin "1") (pinfunction "1_1") (pintype "input"))
      (node (ref "U5") (pin "9") (pinfunction "OCM_9") (pintype "input"))
    )
    (net (code "39") (name "Net-(U8-BSW)") (class "Default")
      (node (ref "U8") (pin "7") (pinfunction "BSW_7") (pintype "output"))
      (node (ref "U9") (pin "1") (pinfunction "G_1") (pintype "input"))
    )
    (net (code "40") (name "Net-(U8-CN)") (class "Default")
      (node (ref "C48") (pin "2") (pinfunction "2_2") (pintype "input"))
      (node (ref "U8") (pin "18") (pinfunction "CN_18") (pintype "unspecified"))
    )
    (net (code "41") (name "Net-(U8-CP)") (class "Default")
      (node (ref "C49") (pin "2") (pinfunction "2_2") (pintype "input"))
      (node (ref "U8") (pin "21") (pinfunction "CP_21") (pintype "unspecified"))
    )
    (net (code "42") (name "Net-(U8-ENN)") (class "Default")
      (node (ref "C43") (pin "1") (pinfunction "1_1") (pintype "input"))
      (node (ref "R20") (pin "2") (pinfunction "2_2") (pintype "input"))
      (node (ref "U8") (pin "10") (pinfunction "ENN_10") (pintype "input"))
      (node (ref "U8") (pin "11") (pinfunction "PSN_11") (pintype "input"))
      (node (ref "U8") (pin "4") (pinfunction "VIN_4") (pintype "unspecified"))
      (node (ref "U8") (pin "8") (pinfunction "ENP_8") (pintype "input"))
      (node (ref "U8") (pin "9") (pinfunction "PSP_9") (pintype "input"))
    )
    (net (code "43") (name "Net-(U8-FBN)") (class "Default")
      (node (ref "C46") (pin "2") (pinfunction "2_2") (pintype "input"))
      (node (ref "R22") (pin "1") (pinfunction "1_1") (pintype "input"))
      (node (ref "R24") (pin "2") (pinfunction "2_2") (pintype "input"))
      (node (ref "U8") (pin "16") (pinfunction "FBN_16") (pintype "input"))
    )
    (net (code "44") (name "Net-(U8-FBP)") (class "Default")
      (node (ref "C44") (pin "1") (pinfunction "1_1") (pintype "input"))
      (node (ref "R21") (pin "1") (pinfunction "1_1") (pintype "input"))
      (node (ref "R23") (pin "2") (pinfunction "2_2") (pintype "input"))
      (node (ref "U8") (pin "22") (pinfunction "FBP_22") (pintype "input"))
    )
    (net (code "45") (name "Net-(U8-VREF)") (class "Default")
      (node (ref "C45") (pin "2") (pinfunction "2_2") (pintype "input"))
      (node (ref "R22") (pin "2") (pinfunction "2_2") (pintype "input"))
      (node (ref "U8") (pin "17") (pinfunction "VREF_17") (pintype "output"))
    )
    (net (code "46") (name "Net-(U9-D)") (class "Default")
      (node (ref "C41") (pin "1") (pinfunction "1_1") (pintype "input"))
      (node (ref "L1") (pin "1") (pinfunction "1_1") (pintype "unspecified"))
      (node (ref "U9") (pin "3") (pinfunction "D_3") (pintype "input"))
    )
    (net (code "47") (name "Net-(U12-OUTN)") (class "Default")
      (node (ref "C54") (pin "1") (pinfunction "1_1") (pintype "input"))
      (node (ref "U12") (pin "7") (pinfunction "OUTN_7") (pintype "input"))
    )
    (net (code "48") (name "Net-(U12-OUTP)") (class "Default")
      (node (ref "C53") (pin "1") (pinfunction "1_1") (pintype "input"))
      (node (ref "U12") (pin "1") (pinfunction "OUTP_1") (pintype "input"))
    )
    (net (code "49") (name "REF1") (class "Default")
      (node (ref "C39") (pin "2") (pinfunction "2_2") (pintype "input"))
      (node (ref "C40") (pin "2") (pinfunction "2_2") (pintype "input"))
      (node (ref "TP1") (pin "1") (pinfunction "1_1") (pintype "input"))
      (node (ref "U1") (pin "3") (pinfunction "REF_3") (pintype "unspecified"))
      (node (ref "U2") (pin "3") (pinfunction "REF_3") (pintype "unspecified"))
      (node (ref "U6") (pin "6") (pinfunction "VOUT_6") (pintype "unspecified"))
    )
    (net (code "50") (name "SCLK1") (class "Default")
      (node (ref "U1") (pin "5") (pinfunction "SCLK_5") (pintype "unspecified"))
      (node (ref "U7") (pin "7") (pinfunction "7_7") (pintype "input"))
    )
    (net (code "51") (name "SCLK2") (class "Default")
      (node (ref "U2") (pin "5") (pinfunction "SCLK_5") (pintype "unspecified"))
      (node (ref "U7") (pin "2") (pinfunction "2_2") (pintype "input"))
    )
    (net (code "52") (name "VIN") (class "Default")
      (node (ref "C42") (pin "1") (pinfunction "1_1") (pintype "input"))
      (node (ref "L3") (pin "1") (pinfunction "1_1") (pintype "unspecified"))
      (node (ref "R20") (pin "1") (pinfunction "1_1") (pintype "input"))
      (node (ref "U8") (pin "5") (pinfunction "INN_5") (pintype "unspecified"))
      (node (ref "U8") (pin "6") (pinfunction "INN_6") (pintype "unspecified"))
      (node (ref "U9") (pin "2") (pinfunction "S_2") (pintype "input"))
      (node (ref "USB1") (pin "2") (pinfunction "VBUS_2") (pintype "unspecified"))
      (node (ref "USB1") (pin "5") (pinfunction "VBUS_5") (pintype "unspecified"))
    )
    (net (code "53") (name "VOUT+") (class "Default")
      (node (ref "RF4") (pin "5") (pinfunction "IN_5") (pintype "unspecified"))
      (node (ref "U5") (pin "11") (pinfunction "OUT-_11") (pintype "input"))
    )
    (net (code "54") (name "VOUT-") (class "Default")
      (node (ref "RF5") (pin "5") (pinfunction "IN_5") (pintype "unspecified"))
      (node (ref "U5") (pin "10") (pinfunction "OUT+_10") (pintype "input"))
    )
    (net (code "55") (name "VOUT1") (class "Default")
      (node (ref "R1") (pin "1") (pinfunction "1_1") (pintype "input"))
      (node (ref "U1") (pin "1") (pinfunction "VOUT_1") (pintype "unspecified"))
    )
    (net (code "56") (name "VOUT2") (class "Default")
      (node (ref "R4") (pin "1") (pinfunction "1_1") (pintype "input"))
      (node (ref "U2") (pin "1") (pinfunction "VOUT_1") (pintype "unspecified"))
    )
    (net (code "57") (name "unconnected-(U3-DIS-Pad12)") (class "Default")
      (node (ref "U3") (pin "12") (pinfunction "DIS_12") (pintype "input+no_connect"))
    )
    (net (code "58") (name "unconnected-(U4-DIS-Pad12)") (class "Default")
      (node (ref "U4") (pin "12") (pinfunction "DIS_12") (pintype "input+no_connect"))
    )
    (net (code "59") (name "unconnected-(U5-DIS-Pad12)") (class "Default")
      (node (ref "U5") (pin "12") (pinfunction "DIS_12") (pintype "input+no_connect"))
    )
    (net (code "60") (name "unconnected-(U6-DNC-Pad1)") (class "Default")
      (node (ref "U6") (pin "1") (pinfunction "DNC_1") (pintype "unspecified+no_connect"))
    )
    (net (code "61") (name "unconnected-(U6-DNC-Pad8)") (class "Default")
      (node (ref "U6") (pin "8") (pinfunction "DNC_8") (pintype "unspecified+no_connect"))
    )
    (net (code "62") (name "unconnected-(U6-NC-Pad7)") (class "Default")
      (node (ref "U6") (pin "7") (pinfunction "NC_7") (pintype "unspecified+no_connect"))
    )
    (net (code "63") (name "unconnected-(U6-TEMP-Pad3)") (class "Default")
      (node (ref "U6") (pin "3") (pinfunction "TEMP_3") (pintype "unspecified+no_connect"))
    )
    (net (code "64") (name "unconnected-(U6-TRIM{slash}NR-Pad5)") (class "Default")
      (node (ref "U6") (pin "5") (pinfunction "TRIM/NR_5") (pintype "unspecified+no_connect"))
    )
    (net (code "65") (name "unconnected-(U8-NC-Pad12)") (class "Default")
      (node (ref "U8") (pin "12") (pinfunction "NC_12") (pintype "unspecified"))
    )
    (net (code "66") (name "unconnected-(U8-NC-Pad20)") (class "Default")
      (node (ref "U8") (pin "20") (pinfunction "NC_20") (pintype "unspecified"))
    )
    (net (code "67") (name "unconnected-(U12-NC-Pad2)") (class "Default")
      (node (ref "U12") (pin "2") (pinfunction "NC_2") (pintype "input+no_connect"))
    )
    (net (code "68") (name "unconnected-(U12-NC-Pad8)") (class "Default")
      (node (ref "U12") (pin "8") (pinfunction "NC_8") (pintype "input+no_connect"))
    )
    (net (code "69") (name "unconnected-(U12-NC-Pad13)") (class "Default")
      (node (ref "U12") (pin "13") (pinfunction "NC_13") (pintype "input+no_connect"))
    )
    (net (code "70") (name "unconnected-(USB1-CC1-Pad3)") (class "Default")
      (node (ref "USB1") (pin "3") (pinfunction "CC1_3") (pintype "unspecified+no_connect"))
    )
    (net (code "71") (name "unconnected-(USB1-CC2-Pad4)") (class "Default")
      (node (ref "USB1") (pin "4") (pinfunction "CC2_4") (pintype "unspecified+no_connect"))
    )
    (net (code "72") (name "unconnected-(USB1-EH-Pad7)") (class "Default")
      (node (ref "USB1") (pin "7") (pinfunction "EH_7") (pintype "unspecified+no_connect"))
    )
  )
)
